# Thermocouple_interface.net
KiCad netlist of a schematic drawn in Altium Designer
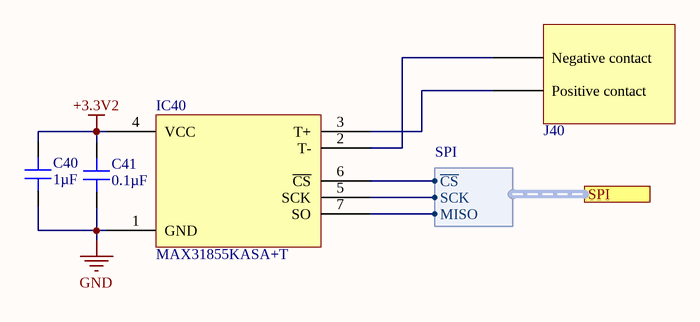
[diagram p0: Thermocouple interface.SchDoc]

(export (version "E")
  (design (tool "Eeschema 10.0.6"))
  (components
    (comp (ref "C40")
      (value "1µF")
      (footprint "CAP 1206_3216 - 1.8MM")
      (description "CAP CER 1UF 50V X7R 1206")
      (fields (field (name "PART NUMBER") "C1206F105M5RACAUTO") (field (name "MANUFACTURER") "KEMET"))
      (libsource (lib "Celestial Altium Library - altium_library") (part "Capacitor"))
    )
    (comp (ref "C41")
      (value "0.1µF")
      (footprint "CAP 1206_3216 - 1.8MM")
      (description "CAP CER 0.1UF 50V X7R 1206")
      (fields (field (name "PART NUMBER") "C1206X104K5RECAUTO") (field (name "MANUFACTURER") "KEMET"))
      (libsource (lib "Celestial Altium Library - altium_library") (part "Capacitor"))
    )
    (comp (ref "IC40")
      (value "MAX31855KASA+T")
      (footprint "MAXIM SOIC-8 S8")
      (description "IC CONV THERMOCOUPLE-DGTL 8SOIC")
      (fields (field (name "MANUFACTURER") "Maxim Integrated"))
      (libsource (lib "Celestial Altium Library - altium_library") (part "Maxim MAX31855"))
    )
    (comp (ref "J40")
      (value "IKM-K-PCB")
      (footprint "IM-K-PCB")
      (description "Miniature Thermocouple PCB Mounting Socket")
      (fields (field (name "MANUFACTURER") "Lab Facility"))
      (libsource (lib "ThermocoupleConnector") (part "IKM-K-PCB"))
    )
  )
  (nets
    (net (code "2") (name "+3.3V2") (class "Default")
      (node (ref "C40") (pin "2") (pinfunction "2_2") (pintype "passive"))
      (node (ref "C41") (pin "2") (pinfunction "2_2") (pintype "passive"))
      (node (ref "IC40") (pin "4") (pinfunction "VCC_4") (pintype "passive"))
    )
    (net (code "3") (name "/MISO") (class "Default")
      (node (ref "IC40") (pin "7") (pinfunction "SO_7") (pintype "passive"))
    )
    (net (code "4") (name "/SCK") (class "Default")
      (node (ref "IC40") (pin "5") (pinfunction "SCK_5") (pintype "passive"))
    )
    (net (code "6") (name "/~{CS}") (class "Default")
      (node (ref "IC40") (pin "6") (pinfunction "~{CS}_6") (pintype "passive"))
    )
    (net (code "7") (name "GND") (class "Default")
      (node (ref "C40") (pin "1") (pinfunction "1_1") (pintype "passive"))
      (node (ref "C41") (pin "1") (pinfunction "1_1") (pintype "passive"))
      (node (ref "IC40") (pin "1") (pinfunction "GND_1") (pintype "passive"))
    )
    (net (code "8") (name "Net-(IC40-T+)") (class "Default")
      (node (ref "IC40") (pin "3") (pinfunction "T+_3") (pintype "passive"))
      (node (ref "J40") (pin "0") (pinfunction "Positive_contact_0") (pintype "passive"))
    )
    (net (code "9") (name "Net-(IC40-T-)") (class "Default")
      (node (ref "IC40") (pin "2") (pinfunction "T-_2") (pintype "passive"))
      (node (ref "J40") (pin "1") (pinfunction "Negative_contact_1") (pintype "passive"))
    )
  )
)
